# Main_board.net
KiCad netlist of a schematic drawn in Altium Designer
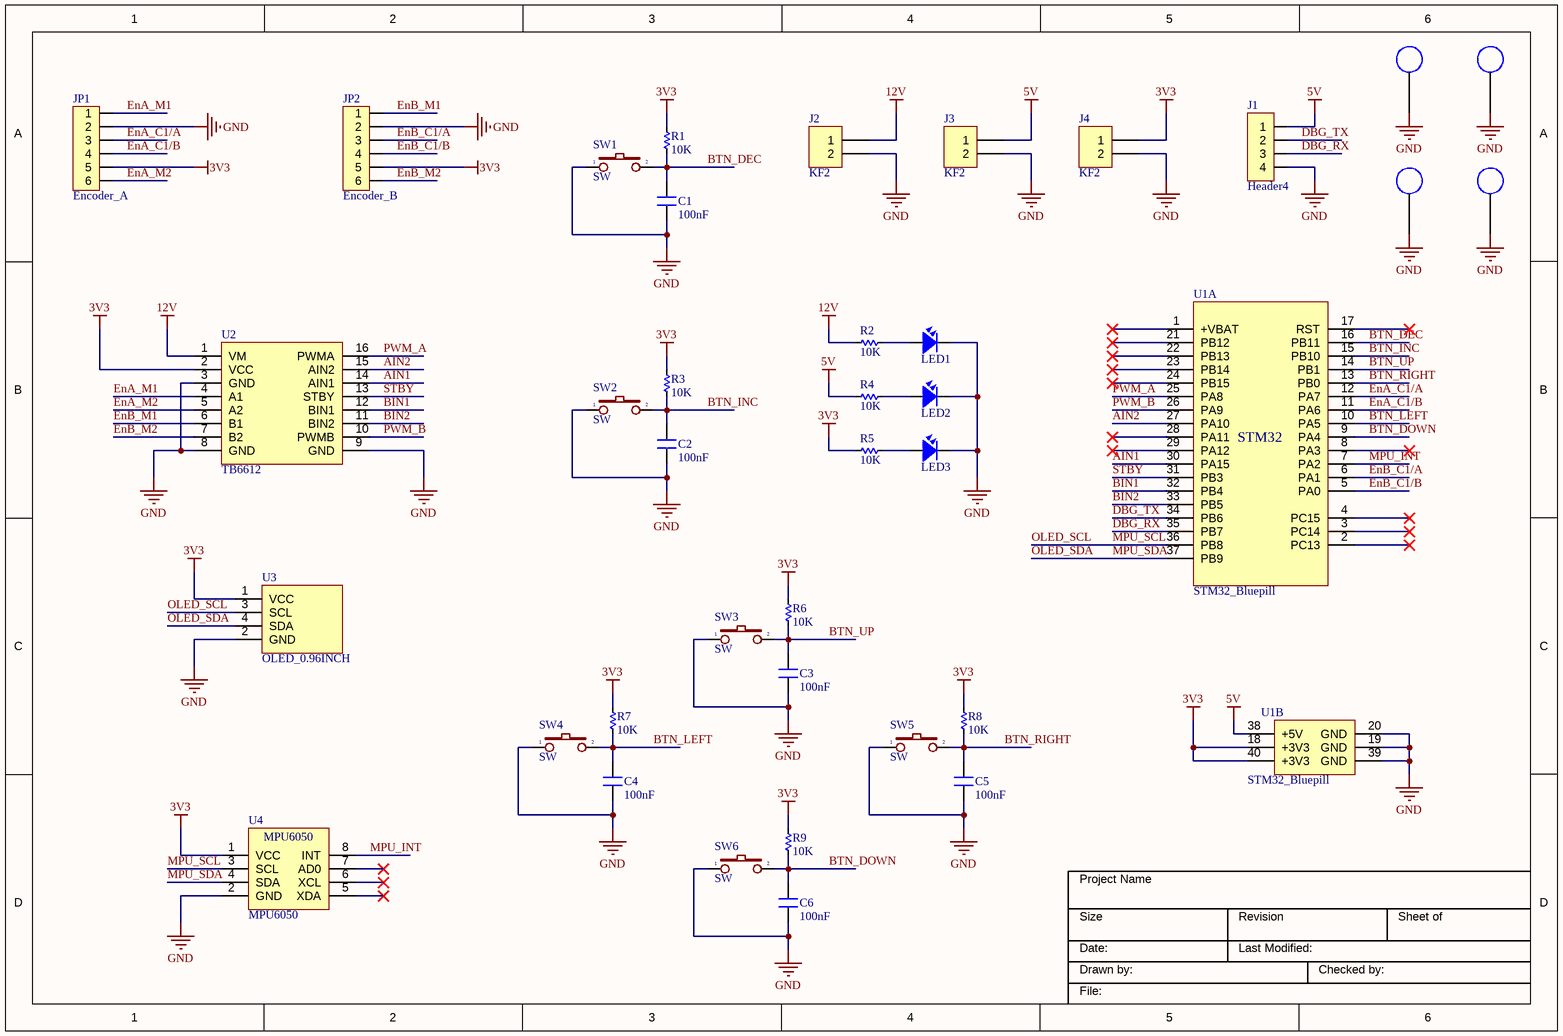
[diagram p0: Main_board.SchDoc]

(export (version "E")
  (design (tool "Eeschema 10.0.6"))
  (components
    (comp (ref "C1") (value "100nF") (footprint "CN1") (libsource (lib "Library") (part "Cap")))
    (comp (ref "C2") (value "100nF") (footprint "CN1") (libsource (lib "Library") (part "Cap")))
    (comp (ref "C3") (value "100nF") (footprint "CN1") (libsource (lib "Library") (part "Cap")))
    (comp (ref "C4") (value "100nF") (footprint "CN1") (libsource (lib "Library") (part "Cap")))
    (comp (ref "C5") (value "100nF") (footprint "CN1") (libsource (lib "Library") (part "Cap")))
    (comp (ref "C6") (value "100nF") (footprint "CN1") (libsource (lib "Library") (part "Cap")))
    (comp (ref "H1") (value "M3") (footprint "M3") (libsource (lib "Library") (part "M3")))
    (comp (ref "H2") (value "M3") (footprint "M3") (libsource (lib "Library") (part "M3")))
    (comp (ref "H3") (value "M3") (footprint "M3") (libsource (lib "Library") (part "M3")))
    (comp (ref "H4") (value "M3") (footprint "M3") (libsource (lib "Library") (part "M3")))
    (comp (ref "J1")
      (value "Header4")
      (footprint "Header4")
      (description "Header IDC, 4 x 1 Pin Vertical 2.54mm Pitch (Non-Boxed, Male)")
      (fields
        (field (name "MANUFACTURER") "Würth Elektronik eiSos GmbH")
        (field (name "PARTNO") "613002143121")
        (field (name "CREATED BY") "Karrer Zheng")
      )
      (libsource (lib "Library") (part "Header4"))
    )
    (comp (ref "J2")
      (value "KF2")
      (footprint "KF2-5.08")
      (fields
        (field (name "MANUFACTURER") "Würth Elektronik eiSos GmbH")
        (field (name "PARTNO") "691103110002")
        (field (name "CREATED BY") "Karrer Zheng")
      )
      (libsource (lib "Library") (part "KF2"))
    )
    (comp (ref "J3")
      (value "KF2")
      (footprint "KF2-5.08")
      (fields
        (field (name "MANUFACTURER") "Würth Elektronik eiSos GmbH")
        (field (name "PARTNO") "691103110002")
        (field (name "CREATED BY") "Karrer Zheng")
      )
      (libsource (lib "Library") (part "KF2"))
    )
    (comp (ref "J4")
      (value "KF2")
      (footprint "KF2-5.08")
      (fields
        (field (name "MANUFACTURER") "Würth Elektronik eiSos GmbH")
        (field (name "PARTNO") "691103110002")
        (field (name "CREATED BY") "Karrer Zheng")
      )
      (libsource (lib "Library") (part "KF2"))
    )
    (comp (ref "JP1")
      (value "Encoder_A")
      (footprint "Header6")
      (description "Header IDC, 6 x 1 Pin Vertical 2.54mm Pitch (Non-Boxed, Male)")
      (fields
        (field (name "MANUFACTURER") "Würth Elektronik eiSos GmbH")
        (field (name "PARTNO") "613002143121")
        (field (name "CREATED BY") "Karrer Zheng")
      )
      (libsource (lib "Library") (part "Header6"))
    )
    (comp (ref "JP2")
      (value "Encoder_B")
      (footprint "Header6")
      (description "Header IDC, 6 x 1 Pin Vertical 2.54mm Pitch (Non-Boxed, Male)")
      (fields
        (field (name "MANUFACTURER") "Würth Elektronik eiSos GmbH")
        (field (name "PARTNO") "613002143121")
        (field (name "CREATED BY") "Karrer Zheng")
      )
      (libsource (lib "Library") (part "Header6"))
    )
    (comp (ref "LED1")
      (value "LED")
      (footprint "LED-3MM-GREEN")
      (description "LED Single colour Green and Red")
      (libsource (lib "Library") (part "LED"))
    )
    (comp (ref "LED2")
      (value "LED")
      (footprint "LED-3MM-GREEN")
      (description "LED Single colour Green and Red")
      (libsource (lib "Library") (part "LED"))
    )
    (comp (ref "LED3")
      (value "LED")
      (footprint "LED-3MM-BLUE")
      (description "LED Single colour Green and Red")
      (libsource (lib "Library") (part "LED"))
    )
    (comp (ref "R1")
      (value "10K")
      (footprint "RES-1/4W-SMALL")
      (description "Res")
      (fields
        (field (name "MANUFACTURER") "Generic Components")
        (field (name "PUBLISHER") "Altium Hobart Technology Centre")
      )
      (libsource (lib "Library") (part "Res"))
    )
    (comp (ref "R2")
      (value "10K")
      (footprint "RES-1/4W-SMALL")
      (description "Res")
      (fields
        (field (name "MANUFACTURER") "Generic Components")
        (field (name "PUBLISHER") "Altium Hobart Technology Centre")
      )
      (libsource (lib "Library") (part "Res"))
    )
    (comp (ref "R3")
      (value "10K")
      (footprint "RES-1/4W-SMALL")
      (description "Res")
      (fields
        (field (name "MANUFACTURER") "Generic Components")
        (field (name "PUBLISHER") "Altium Hobart Technology Centre")
      )
      (libsource (lib "Library") (part "Res"))
    )
    (comp (ref "R4")
      (value "10K")
      (footprint "RES-1/4W-SMALL")
      (description "Res")
      (fields
        (field (name "MANUFACTURER") "Generic Components")
        (field (name "PUBLISHER") "Altium Hobart Technology Centre")
      )
      (libsource (lib "Library") (part "Res"))
    )
    (comp (ref "R5")
      (value "10K")
      (footprint "RES-1/4W-SMALL")
      (description "Res")
      (fields
        (field (name "MANUFACTURER") "Generic Components")
        (field (name "PUBLISHER") "Altium Hobart Technology Centre")
      )
      (libsource (lib "Library") (part "Res"))
    )
    (comp (ref "R6")
      (value "10K")
      (footprint "RES-1/4W-SMALL")
      (description "Res")
      (fields
        (field (name "MANUFACTURER") "Generic Components")
        (field (name "PUBLISHER") "Altium Hobart Technology Centre")
      )
      (libsource (lib "Library") (part "Res"))
    )
    (comp (ref "R7")
      (value "10K")
      (footprint "RES-1/4W-SMALL")
      (description "Res")
      (fields
        (field (name "MANUFACTURER") "Generic Components")
        (field (name "PUBLISHER") "Altium Hobart Technology Centre")
      )
      (libsource (lib "Library") (part "Res"))
    )
    (comp (ref "R8")
      (value "10K")
      (footprint "RES-1/4W-SMALL")
      (description "Res")
      (fields
        (field (name "MANUFACTURER") "Generic Components")
        (field (name "PUBLISHER") "Altium Hobart Technology Centre")
      )
      (libsource (lib "Library") (part "Res"))
    )
    (comp (ref "R9")
      (value "10K")
      (footprint "RES-1/4W-SMALL")
      (description "Res")
      (fields
        (field (name "MANUFACTURER") "Generic Components")
        (field (name "PUBLISHER") "Altium Hobart Technology Centre")
      )
      (libsource (lib "Library") (part "Res"))
    )
    (comp (ref "SW1")
      (value "SW")
      (footprint "SW1-DIP-12x12x8-Red")
      (description "Switch button 2 pin")
      (libsource (lib "Library") (part "SW2"))
    )
    (comp (ref "SW2")
      (value "SW")
      (footprint "SW1-DIP-12x12x8-Red")
      (description "Switch button 2 pin")
      (libsource (lib "Library") (part "SW2"))
    )
    (comp (ref "SW3")
      (value "SW")
      (footprint "SW1-DIP-12x12x8-Red")
      (description "Switch button 2 pin")
      (libsource (lib "Library") (part "SW2"))
    )
    (comp (ref "SW4")
      (value "SW")
      (footprint "SW1-DIP-12x12x8-Red")
      (description "Switch button 2 pin")
      (libsource (lib "Library") (part "SW2"))
    )
    (comp (ref "SW5")
      (value "SW")
      (footprint "SW1-DIP-12x12x8-Red")
      (description "Switch button 2 pin")
      (libsource (lib "Library") (part "SW2"))
    )
    (comp (ref "SW6")
      (value "SW")
      (footprint "SW1-DIP-12x12x8-Red")
      (description "Switch button 2 pin")
      (libsource (lib "Library") (part "SW2"))
    )
    (comp (ref "U1")
      (value "STM32_Bluepill")
      (footprint "STM32F103_BluePill")
      (libsource (lib "Library") (part "STM32_Bluepill"))
    )
    (comp (ref "U2") (value "TB6612") (footprint "TB6612") (libsource (lib "Library") (part "TB6612")))
    (comp (ref "U3")
      (value "OLED_0.96INCH")
      (footprint "OLED_0.96-inch")
      (libsource (lib "Library") (part "OLED_0.96INCH"))
    )
    (comp (ref "U4")
      (value "MPU6050")
      (footprint "MPU6050")
      (fields
        (field (name "MANUFACTURER") "Würth Elektronik eiSos GmbH")
        (field (name "PARTNO") "613004143121")
        (field (name "CREATED BY") "Karrer Zheng")
      )
      (libsource (lib "Library") (part "MPU6050"))
    )
  )
  (nets
    (net (code "1") (name "/AIN1") (class "Default")
      (node (ref "U1") (pin "30") (pinfunction "PA15_30") (pintype "passive"))
      (node (ref "U2") (pin "14") (pinfunction "AIN1_14") (pintype "passive"))
    )
    (net (code "2") (name "/AIN2") (class "Default")
      (node (ref "U1") (pin "27") (pinfunction "PA10_27") (pintype "passive"))
      (node (ref "U2") (pin "15") (pinfunction "AIN2_15") (pintype "passive"))
    )
    (net (code "3") (name "/BIN1") (class "Default")
      (node (ref "U1") (pin "32") (pinfunction "PB4_32") (pintype "passive"))
      (node (ref "U2") (pin "12") (pinfunction "BIN1_12") (pintype "passive"))
    )
    (net (code "4") (name "/BIN2") (class "Default")
      (node (ref "U1") (pin "33") (pinfunction "PB5_33") (pintype "passive"))
      (node (ref "U2") (pin "11") (pinfunction "BIN2_11") (pintype "passive"))
    )
    (net (code "5") (name "/BTN_DEC") (class "Default")
      (node (ref "C1") (pin "2") (pinfunction "2_2") (pintype "passive"))
      (node (ref "R1") (pin "2") (pinfunction "2_2") (pintype "passive"))
      (node (ref "SW1") (pin "2") (pinfunction "2_2") (pintype "passive"))
      (node (ref "U1") (pin "16") (pinfunction "PB11_16") (pintype "passive"))
    )
    (net (code "6") (name "/BTN_DOWN") (class "Default")
      (node (ref "C6") (pin "2") (pinfunction "2_2") (pintype "passive"))
      (node (ref "R9") (pin "2") (pinfunction "2_2") (pintype "passive"))
      (node (ref "SW6") (pin "2") (pinfunction "2_2") (pintype "passive"))
      (node (ref "U1") (pin "9") (pinfunction "PA4_9") (pintype "passive"))
    )
    (net (code "7") (name "/BTN_INC") (class "Default")
      (node (ref "C2") (pin "2") (pinfunction "2_2") (pintype "passive"))
      (node (ref "R3") (pin "2") (pinfunction "2_2") (pintype "passive"))
      (node (ref "SW2") (pin "2") (pinfunction "2_2") (pintype "passive"))
      (node (ref "U1") (pin "15") (pinfunction "PB10_15") (pintype "passive"))
    )
    (net (code "8") (name "/BTN_LEFT") (class "Default")
      (node (ref "C4") (pin "2") (pinfunction "2_2") (pintype "passive"))
      (node (ref "R7") (pin "2") (pinfunction "2_2") (pintype "passive"))
      (node (ref "SW4") (pin "2") (pinfunction "2_2") (pintype "passive"))
      (node (ref "U1") (pin "10") (pinfunction "PA5_10") (pintype "passive"))
    )
    (net (code "9") (name "/BTN_RIGHT") (class "Default")
      (node (ref "C5") (pin "2") (pinfunction "2_2") (pintype "passive"))
      (node (ref "R8") (pin "2") (pinfunction "2_2") (pintype "passive"))
      (node (ref "SW5") (pin "2") (pinfunction "2_2") (pintype "passive"))
      (node (ref "U1") (pin "13") (pinfunction "PB0_13") (pintype "passive"))
    )
    (net (code "10") (name "/BTN_UP") (class "Default")
      (node (ref "C3") (pin "2") (pinfunction "2_2") (pintype "passive"))
      (node (ref "R6") (pin "2") (pinfunction "2_2") (pintype "passive"))
      (node (ref "SW3") (pin "2") (pinfunction "2_2") (pintype "passive"))
      (node (ref "U1") (pin "14") (pinfunction "PB1_14") (pintype "passive"))
    )
    (net (code "11") (name "/DBG_RX") (class "Default")
      (node (ref "J1") (pin "3") (pinfunction "3_3") (pintype "passive"))
      (node (ref "U1") (pin "35") (pinfunction "PB7_35") (pintype "passive"))
    )
    (net (code "12") (name "/DBG_TX") (class "Default")
      (node (ref "J1") (pin "2") (pinfunction "2_2") (pintype "passive"))
      (node (ref "U1") (pin "34") (pinfunction "PB6_34") (pintype "passive"))
    )
    (net (code "13") (name "/EnA_C1{slash}A") (class "Default")
      (node (ref "JP1") (pin "3") (pinfunction "3_3") (pintype "passive"))
      (node (ref "U1") (pin "12") (pinfunction "PA7_12") (pintype "passive"))
    )
    (net (code "14") (name "/EnA_C1{slash}B") (class "Default")
      (node (ref "JP1") (pin "4") (pinfunction "4_4") (pintype "passive"))
      (node (ref "U1") (pin "11") (pinfunction "PA6_11") (pintype "passive"))
    )
    (net (code "15") (name "/EnA_M1") (class "Default")
      (node (ref "JP1") (pin "1") (pinfunction "1_1") (pintype "passive"))
      (node (ref "U2") (pin "4") (pinfunction "A1_4") (pintype "passive"))
    )
    (net (code "16") (name "/EnA_M2") (class "Default")
      (node (ref "JP1") (pin "6") (pinfunction "6_6") (pintype "passive"))
      (node (ref "U2") (pin "5") (pinfunction "A2_5") (pintype "passive"))
    )
    (net (code "17") (name "/EnB_C1{slash}A") (class "Default")
      (node (ref "JP2") (pin "3") (pinfunction "3_3") (pintype "passive"))
      (node (ref "U1") (pin "6") (pinfunction "PA1_6") (pintype "passive"))
    )
    (net (code "18") (name "/EnB_C1{slash}B") (class "Default")
      (node (ref "JP2") (pin "4") (pinfunction "4_4") (pintype "passive"))
      (node (ref "U1") (pin "5") (pinfunction "PA0_5") (pintype "passive"))
    )
    (net (code "19") (name "/EnB_M1") (class "Default")
      (node (ref "JP2") (pin "1") (pinfunction "1_1") (pintype "passive"))
      (node (ref "U2") (pin "6") (pinfunction "B1_6") (pintype "passive"))
    )
    (net (code "20") (name "/EnB_M2") (class "Default")
      (node (ref "JP2") (pin "6") (pinfunction "6_6") (pintype "passive"))
      (node (ref "U2") (pin "7") (pinfunction "B2_7") (pintype "passive"))
    )
    (net (code "21") (name "/MPU_INT") (class "Default")
      (node (ref "U1") (pin "7") (pinfunction "PA2_7") (pintype "passive"))
      (node (ref "U4") (pin "8") (pinfunction "INT_8") (pintype "passive"))
    )
    (net (code "22") (name "/MPU_SCL") (class "Default")
      (node (ref "U1") (pin "36") (pinfunction "PB8_36") (pintype "passive"))
      (node (ref "U3") (pin "3") (pinfunction "SCL_3") (pintype "passive"))
      (node (ref "U4") (pin "3") (pinfunction "SCL_3") (pintype "passive"))
    )
    (net (code "23") (name "/MPU_SDA") (class "Default")
      (node (ref "U1") (pin "37") (pinfunction "PB9_37") (pintype "passive"))
      (node (ref "U3") (pin "4") (pinfunction "SDA_4") (pintype "passive"))
      (node (ref "U4") (pin "4") (pinfunction "SDA_4") (pintype "passive"))
    )
    (net (code "24") (name "/PWM_A") (class "Default")
      (node (ref "U1") (pin "25") (pinfunction "PA8_25") (pintype "passive"))
      (node (ref "U2") (pin "16") (pinfunction "PWMA_16") (pintype "passive"))
    )
    (net (code "25") (name "/PWM_B") (class "Default")
      (node (ref "U1") (pin "26") (pinfunction "PA9_26") (pintype "passive"))
      (node (ref "U2") (pin "10") (pinfunction "PWMB_10") (pintype "passive"))
    )
    (net (code "26") (name "/STBY") (class "Default")
      (node (ref "U1") (pin "31") (pinfunction "PB3_31") (pintype "passive"))
      (node (ref "U2") (pin "13") (pinfunction "STBY_13") (pintype "passive"))
    )
    (net (code "27") (name "3V3") (class "Default")
      (node (ref "J4") (pin "1") (pinfunction "1_1") (pintype "passive"))
      (node (ref "JP1") (pin "5") (pinfunction "5_5") (pintype "passive"))
      (node (ref "JP2") (pin "5") (pinfunction "5_5") (pintype "passive"))
      (node (ref "R1") (pin "1") (pinfunction "1_1") (pintype "passive"))
      (node (ref "R3") (pin "1") (pinfunction "1_1") (pintype "passive"))
      (node (ref "R5") (pin "1") (pinfunction "1_1") (pintype "passive"))
      (node (ref "R6") (pin "1") (pinfunction "1_1") (pintype "passive"))
      (node (ref "R7") (pin "1") (pinfunction "1_1") (pintype "passive"))
      (node (ref "R8") (pin "1") (pinfunction "1_1") (pintype "passive"))
      (node (ref "R9") (pin "1") (pinfunction "1_1") (pintype "passive"))
      (node (ref "U1") (pin "18") (pinfunction "+3V3_18") (pintype "passive"))
      (node (ref "U1") (pin "40") (pinfunction "+3V3_40") (pintype "passive"))
      (node (ref "U2") (pin "2") (pinfunction "VCC_2") (pintype "passive"))
      (node (ref "U3") (pin "1") (pinfunction "VCC_1") (pintype "passive"))
      (node (ref "U4") (pin "1") (pinfunction "VCC_1") (pintype "passive"))
    )
    (net (code "28") (name "5V") (class "Default")
      (node (ref "J1") (pin "1") (pinfunction "1_1") (pintype "passive"))
      (node (ref "J3") (pin "1") (pinfunction "1_1") (pintype "passive"))
      (node (ref "R4") (pin "1") (pinfunction "1_1") (pintype "passive"))
      (node (ref "U1") (pin "38") (pinfunction "+5V_38") (pintype "passive"))
    )
    (net (code "29") (name "12V") (class "Default")
      (node (ref "J2") (pin "1") (pinfunction "1_1") (pintype "passive"))
      (node (ref "R2") (pin "1") (pinfunction "1_1") (pintype "passive"))
      (node (ref "U2") (pin "1") (pinfunction "VM_1") (pintype "passive"))
    )
    (net (code "30") (name "GND") (class "Default")
      (node (ref "C1") (pin "1") (pinfunction "1_1") (pintype "passive"))
      (node (ref "C2") (pin "1") (pinfunction "1_1") (pintype "passive"))
      (node (ref "C3") (pin "1") (pinfunction "1_1") (pintype "passive"))
      (node (ref "C4") (pin "1") (pinfunction "1_1") (pintype "passive"))
      (node (ref "C5") (pin "1") (pinfunction "1_1") (pintype "passive"))
      (node (ref "C6") (pin "1") (pinfunction "1_1") (pintype "passive"))
      (node (ref "H1") (pin "1") (pinfunction "76_1") (pintype "passive"))
      (node (ref "H2") (pin "1") (pinfunction "76_1") (pintype "passive"))
      (node (ref "H3") (pin "1") (pinfunction "76_1") (pintype "passive"))
      (node (ref "H4") (pin "1") (pinfunction "76_1") (pintype "passive"))
      (node (ref "J1") (pin "4") (pinfunction "4_4") (pintype "passive"))
      (node (ref "J2") (pin "2") (pinfunction "2_2") (pintype "passive"))
      (node (ref "J3") (pin "2") (pinfunction "2_2") (pintype "passive"))
      (node (ref "J4") (pin "2") (pinfunction "2_2") (pintype "passive"))
      (node (ref "JP1") (pin "2") (pinfunction "2_2") (pintype "passive"))
      (node (ref "JP2") (pin "2") (pinfunction "2_2") (pintype "passive"))
      (node (ref "LED1") (pin "2") (pinfunction "2_2") (pintype "passive"))
      (node (ref "LED2") (pin "2") (pinfunction "2_2") (pintype "passive"))
      (node (ref "LED3") (pin "2") (pinfunction "2_2") (pintype "passive"))
      (node (ref "SW1") (pin "1") (pinfunction "1_1") (pintype "passive"))
      (node (ref "SW2") (pin "1") (pinfunction "1_1") (pintype "passive"))
      (node (ref "SW3") (pin "1") (pinfunction "1_1") (pintype "passive"))
      (node (ref "SW4") (pin "1") (pinfunction "1_1") (pintype "passive"))
      (node (ref "SW5") (pin "1") (pinfunction "1_1") (pintype "passive"))
      (node (ref "SW6") (pin "1") (pinfunction "1_1") (pintype "passive"))
      (node (ref "U1") (pin "19") (pinfunction "GND_19") (pintype "passive"))
      (node (ref "U1") (pin "20") (pinfunction "GND_20") (pintype "passive"))
      (node (ref "U1") (pin "39") (pinfunction "GND_39") (pintype "passive"))
      (node (ref "U2") (pin "3") (pinfunction "GND_3") (pintype "passive"))
      (node (ref "U2") (pin "8") (pinfunction "GND_8") (pintype "passive"))
      (node (ref "U2") (pin "9") (pinfunction "GND_9") (pintype "passive"))
      (node (ref "U3") (pin "2") (pinfunction "GND_2") (pintype "passive"))
      (node (ref "U4") (pin "2") (pinfunction "GND_2") (pintype "passive"))
    )
    (net (code "31") (name "Net-(LED1-Pad1)") (class "Default")
      (node (ref "LED1") (pin "1") (pinfunction "1_1") (pintype "passive"))
      (node (ref "R2") (pin "2") (pinfunction "2_2") (pintype "passive"))
    )
    (net (code "32") (name "Net-(LED2-Pad1)") (class "Default")
      (node (ref "LED2") (pin "1") (pinfunction "1_1") (pintype "passive"))
      (node (ref "R4") (pin "2") (pinfunction "2_2") (pintype "passive"))
    )
    (net (code "33") (name "Net-(LED3-Pad1)") (class "Default")
      (node (ref "LED3") (pin "1") (pinfunction "1_1") (pintype "passive"))
      (node (ref "R5") (pin "2") (pinfunction "2_2") (pintype "passive"))
    )
    (net (code "34") (name "unconnected-(U1A-+VBAT-Pad1)") (class "Default")
      (node (ref "U1") (pin "1") (pinfunction "+VBAT_1") (pintype "passive+no_connect"))
    )
    (net (code "35") (name "unconnected-(U1A-PA3-Pad8)") (class "Default")
      (node (ref "U1") (pin "8") (pinfunction "PA3_8") (pintype "passive+no_connect"))
    )
    (net (code "36") (name "unconnected-(U1A-PA11-Pad28)") (class "Default")
      (node (ref "U1") (pin "28") (pinfunction "PA11_28") (pintype "passive+no_connect"))
    )
    (net (code "37") (name "unconnected-(U1A-PA12-Pad29)") (class "Default")
      (node (ref "U1") (pin "29") (pinfunction "PA12_29") (pintype "passive+no_connect"))
    )
    (net (code "38") (name "unconnected-(U1A-PB12-Pad21)") (class "Default")
      (node (ref "U1") (pin "21") (pinfunction "PB12_21") (pintype "passive+no_connect"))
    )
    (net (code "39") (name "unconnected-(U1A-PB13-Pad22)") (class "Default")
      (node (ref "U1") (pin "22") (pinfunction "PB13_22") (pintype "passive+no_connect"))
    )
    (net (code "40") (name "unconnected-(U1A-PB14-Pad23)") (class "Default")
      (node (ref "U1") (pin "23") (pinfunction "PB14_23") (pintype "passive+no_connect"))
    )
    (net (code "41") (name "unconnected-(U1A-PB15-Pad24)") (class "Default")
      (node (ref "U1") (pin "24") (pinfunction "PB15_24") (pintype "passive+no_connect"))
    )
    (net (code "42") (name "unconnected-(U1A-PC13-Pad2)") (class "Default")
      (node (ref "U1") (pin "2") (pinfunction "PC13_2") (pintype "passive+no_connect"))
    )
    (net (code "43") (name "unconnected-(U1A-PC14-Pad3)") (class "Default")
      (node (ref "U1") (pin "3") (pinfunction "PC14_3") (pintype "passive+no_connect"))
    )
    (net (code "44") (name "unconnected-(U1A-PC15-Pad4)") (class "Default")
      (node (ref "U1") (pin "4") (pinfunction "PC15_4") (pintype "passive+no_connect"))
    )
    (net (code "45") (name "unconnected-(U1A-RST-Pad17)") (class "Default")
      (node (ref "U1") (pin "17") (pinfunction "RST_17") (pintype "passive+no_connect"))
    )
    (net (code "46") (name "unconnected-(U4-AD0-Pad7)") (class "Default")
      (node (ref "U4") (pin "7") (pinfunction "AD0_7") (pintype "passive+no_connect"))
    )
    (net (code "47") (name "unconnected-(U4-XCL-Pad6)") (class "Default")
      (node (ref "U4") (pin "6") (pinfunction "XCL_6") (pintype "passive+no_connect"))
    )
    (net (code "48") (name "unconnected-(U4-XDA-Pad5)") (class "Default")
      (node (ref "U4") (pin "5") (pinfunction "XDA_5") (pintype "passive+no_connect"))
    )
  )
)
